# AUDIO_AMP.net
KiCad netlist of a schematic drawn in Altium Designer
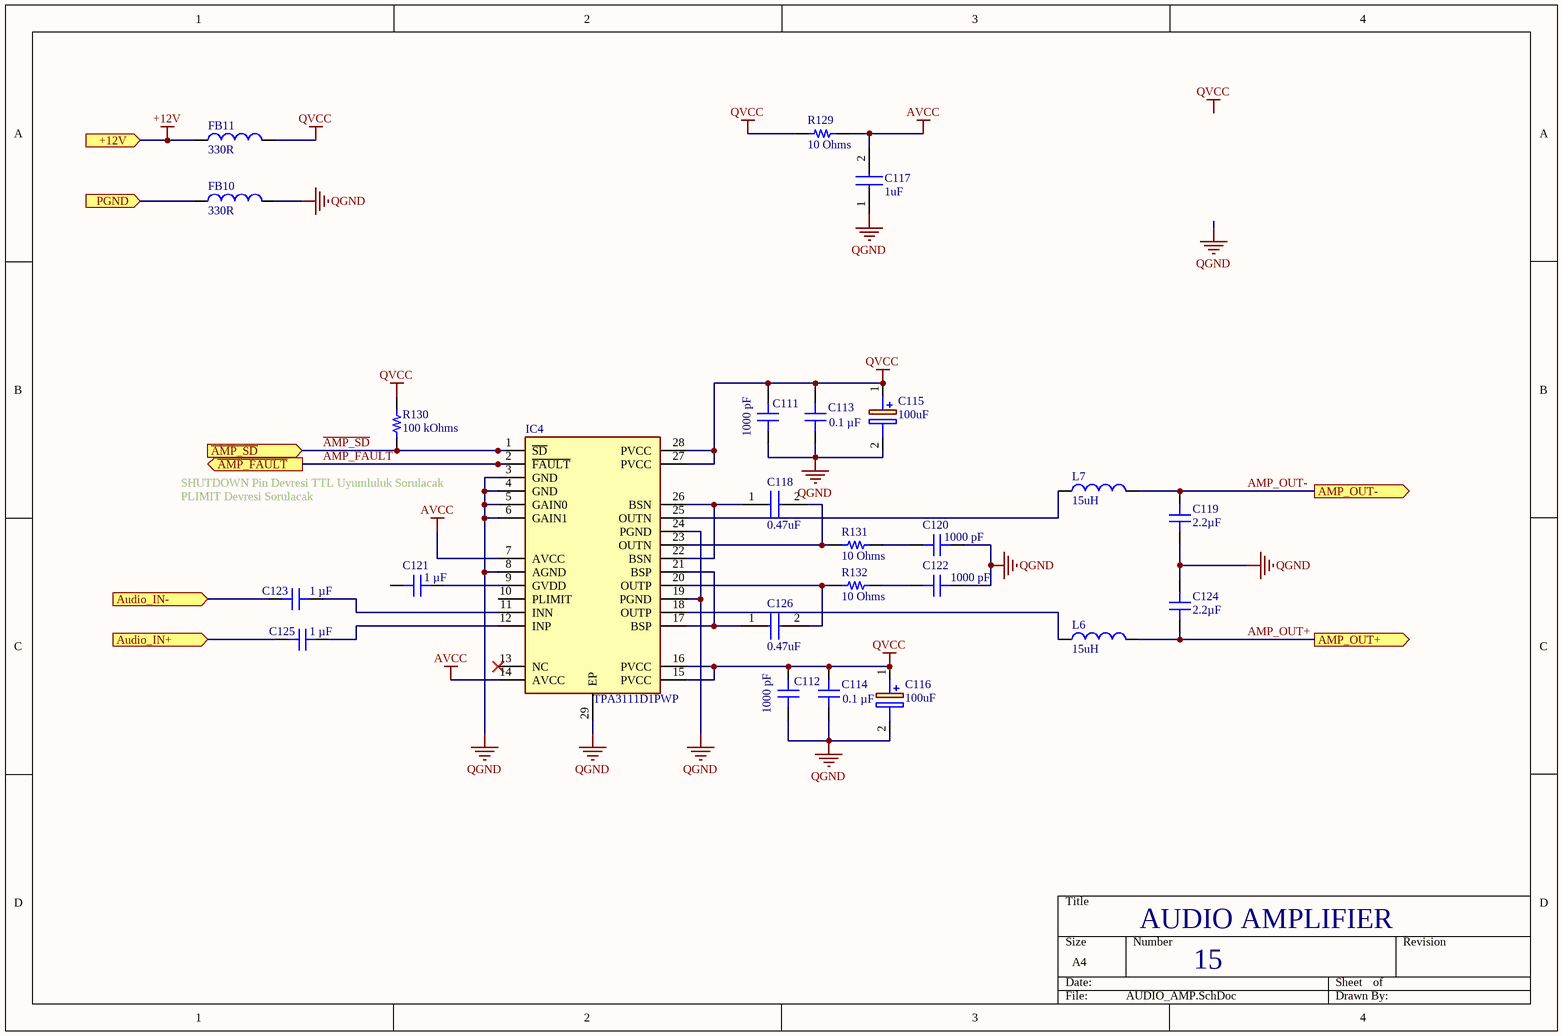
[diagram p0: AUDIO_AMP.SchDoc]

(export (version "E")
  (design (tool "Eeschema 10.0.6"))
  (components
    (comp (ref "C111")
      (value "1000 pF")
      (footprint "CAP 0603_1608")
      (description "CAP CER 1000PF 50V X8R 0603")
      (fields
        (field (name "PART NUMBER") "C1608X8R1H102K080AA")
        (field (name "MANUFACTURER") "TDK Corporation")
      )
      (libsource (lib "Celestial Altium Library") (part "Capacitor"))
    )
    (comp (ref "C112")
      (value "1000 pF")
      (footprint "CAP 0603_1608")
      (description "CAP CER 1000PF 50V X8R 0603")
      (fields
        (field (name "PART NUMBER") "C1608X8R1H102K080AA")
        (field (name "MANUFACTURER") "TDK Corporation")
      )
      (libsource (lib "Celestial Altium Library") (part "Capacitor"))
    )
    (comp (ref "C113")
      (value "0.1 µF")
      (footprint "CAP 0603_1608")
      (description "CAP CER 0.1UF 50V X7R 0603")
      (fields
        (field (name "PART NUMBER") "CGA3E2X7R1H104K080AE")
        (field (name "MANUFACTURER") "TDK Corporation")
      )
      (libsource (lib "Celestial Altium Library") (part "Capacitor"))
    )
    (comp (ref "C114")
      (value "0.1 µF")
      (footprint "CAP 0603_1608")
      (description "CAP CER 0.1UF 50V X7R 0603")
      (fields
        (field (name "PART NUMBER") "CGA3E2X7R1H104K080AE")
        (field (name "MANUFACTURER") "TDK Corporation")
      )
      (libsource (lib "Celestial Altium Library") (part "Capacitor"))
    )
    (comp (ref "C115")
      (value "100uF")
      (footprint "SamacSys:EEE0JA331XP")
      (description "Capacitor Polarised")
      (fields
        (field (name "MANUFACTURER_PART_NUMBER") "EEE-1VA101XP")
        (field (name "MOUSER PART NUMBER") "667-EEE-1VA101XP")
      )
      (libsource (lib "SamacSys") (part "EEE-1VA101XP"))
    )
    (comp (ref "C116")
      (value "100uF")
      (footprint "SamacSys:EEE0JA331XP")
      (description "Capacitor Polarised")
      (fields
        (field (name "MANUFACTURER_PART_NUMBER") "EEE-1VA101XP")
        (field (name "MOUSER PART NUMBER") "667-EEE-1VA101XP")
      )
      (libsource (lib "SamacSys") (part "EEE-1VA101XP"))
    )
    (comp (ref "C117")
      (value "1uF")
      (footprint "SamacSys:CAPC1608X90N")
      (description "Capacitor")
      (fields
        (field (name "MANUFACTURER_PART_NUMBER") "GMK107BJ105KA-T")
        (field (name "MOUSER PART NUMBER") "963-GMK107BJ105KA-T")
      )
      (libsource (lib "SamacSys") (part "GMK107BJ105KA-T"))
    )
    (comp (ref "C118")
      (value "0.47uF")
      (footprint "SamacSys:CAPC1608X90N")
      (description "Capacitor")
      (fields
        (field (name "MANUFACTURER_PART_NUMBER") "0603YD474KAT2A")
        (field (name "MOUSER PART NUMBER") "581-0603YD474K")
      )
      (libsource (lib "SamacSys") (part "0603YD474KAT2A"))
    )
    (comp (ref "C119")
      (value "2.2µF")
      (footprint "CAP 1206_3216 - 1.8MM")
      (description "CAP CER 2.2UF 50V X7R 1206")
      (fields (field (name "PART NUMBER") "12065C225K4T2A") (field (name "MANUFACTURER") "AVX Corporation"))
      (libsource (lib "Celestial Altium Library") (part "Capacitor"))
    )
    (comp (ref "C120")
      (value "1000 pF")
      (footprint "CAP 0603_1608")
      (description "CAP CER 1000PF 50V X8R 0603")
      (fields
        (field (name "PART NUMBER") "C1608X8R1H102K080AA")
        (field (name "MANUFACTURER") "TDK Corporation")
      )
      (libsource (lib "Celestial Altium Library") (part "Capacitor"))
    )
    (comp (ref "C121")
      (value "1 µF")
      (footprint "CAP 0603_1608")
      (description "CAP CER 1UF 16V X5R 0603")
      (fields (field (name "PART NUMBER") "C0603C105K4PAC7867") (field (name "MANUFACTURER") "KEMET"))
      (libsource (lib "Celestial Altium Library") (part "Capacitor"))
    )
    (comp (ref "C122")
      (value "1000 pF")
      (footprint "CAP 0603_1608")
      (description "CAP CER 1000PF 50V X8R 0603")
      (fields
        (field (name "PART NUMBER") "C1608X8R1H102K080AA")
        (field (name "MANUFACTURER") "TDK Corporation")
      )
      (libsource (lib "Celestial Altium Library") (part "Capacitor"))
    )
    (comp (ref "C123")
      (value "1 µF")
      (footprint "CAP 0603_1608")
      (description "CAP CER 1UF 16V X5R 0603")
      (fields (field (name "PART NUMBER") "C0603C105K4PAC7867") (field (name "MANUFACTURER") "KEMET"))
      (libsource (lib "Celestial Altium Library") (part "Capacitor"))
    )
    (comp (ref "C124")
      (value "2.2µF")
      (footprint "CAP 1206_3216 - 1.8MM")
      (description "CAP CER 2.2UF 50V X7R 1206")
      (fields (field (name "PART NUMBER") "12065C225K4T2A") (field (name "MANUFACTURER") "AVX Corporation"))
      (libsource (lib "Celestial Altium Library") (part "Capacitor"))
    )
    (comp (ref "C125")
      (value "1 µF")
      (footprint "CAP 0603_1608")
      (description "CAP CER 1UF 16V X5R 0603")
      (fields (field (name "PART NUMBER") "C0603C105K4PAC7867") (field (name "MANUFACTURER") "KEMET"))
      (libsource (lib "Celestial Altium Library") (part "Capacitor"))
    )
    (comp (ref "C126")
      (value "0.47uF")
      (footprint "SamacSys:CAPC1608X90N")
      (description "Capacitor")
      (fields
        (field (name "MANUFACTURER_PART_NUMBER") "0603YD474KAT2A")
        (field (name "MOUSER PART NUMBER") "581-0603YD474K")
      )
      (libsource (lib "SamacSys") (part "0603YD474KAT2A"))
    )
    (comp (ref "FB10")
      (value "330R")
      (footprint "FB0805")
      (description "FERRITE BEAD 330 OHM 0805 1LN")
      (libsource (lib "ECU") (part "FB0805_330R@100MHz"))
    )
    (comp (ref "FB11")
      (value "330R")
      (footprint "FB0805")
      (description "FERRITE BEAD 330 OHM 0805 1LN")
      (libsource (lib "ECU") (part "FB0805_330R@100MHz"))
    )
    (comp (ref "IC4")
      (value "TPA3111D1PWP")
      (footprint "SOP65P640X120-29N")
      (description "Integrated Circuit")
      (fields (field (name "MOUSER PART NUMBER") "595-TPA3111D1PWP"))
      (libsource (lib "SamacSys") (part "TPA3111D1PWP"))
    )
    (comp (ref "L6")
      (value "15uH")
      (footprint "IND_DG6045C")
      (description "FIXED IND 15UH 2.5A 75.6 MOHM")
      (libsource (lib "ECU") (part "IND_1255AY-150M=P3"))
    )
    (comp (ref "L7")
      (value "15uH")
      (footprint "IND_DG6045C")
      (description "FIXED IND 15UH 2.5A 75.6 MOHM")
      (libsource (lib "ECU") (part "IND_1255AY-150M=P3"))
    )
    (comp (ref "R129")
      (value "10 Ohms")
      (footprint "RES 1206_3216")
      (description "RESISTOR THICK FILM 1206")
      (fields
        (field (name "PART NUMBER") "RK73G2BTTD10R0F")
        (field (name "MANUFACTURER") "KOA Speer Electronics, Inc.")
      )
      (libsource (lib "Celestial Altium Library") (part "Resistor"))
    )
    (comp (ref "R130")
      (value "100 kOhms")
      (footprint "RES 0603_1608")
      (description "RES 100K OHM 5% 1/10W 0603")
      (fields
        (field (name "PART NUMBER") "RMCF0603JT100K")
        (field (name "MANUFACTURER") "Stackpole Electronics Inc")
      )
      (libsource (lib "Celestial Altium Library") (part "Resistor"))
    )
    (comp (ref "R131")
      (value "10 Ohms")
      (footprint "RES 0805_2012")
      (description "RCC0805 100 10R 1% ET1 E3")
      (fields (field (name "PART NUMBER") "RCC080510R0FKEA") (field (name "MANUFACTURER") "Vishay Dale"))
      (libsource (lib "Celestial Altium Library") (part "Resistor"))
    )
    (comp (ref "R132")
      (value "10 Ohms")
      (footprint "RES 0805_2012")
      (description "RCC0805 100 10R 1% ET1 E3")
      (fields (field (name "PART NUMBER") "RCC080510R0FKEA") (field (name "MANUFACTURER") "Vishay Dale"))
      (libsource (lib "Celestial Altium Library") (part "Resistor"))
    )
  )
  (nets
    (net (code "1") (name "+12V") (class "Default")
      (node (ref "FB11") (pin "1") (pinfunction "1_1") (pintype "passive"))
    )
    (net (code "2") (name "/AMP_OUT+") (class "Default")
      (node (ref "C124") (pin "1") (pinfunction "1_1") (pintype "passive"))
      (node (ref "L6") (pin "2") (pinfunction "2_2") (pintype "passive"))
    )
    (net (code "3") (name "/AMP_OUT-") (class "Default")
      (node (ref "C119") (pin "2") (pinfunction "2_2") (pintype "passive"))
      (node (ref "L7") (pin "2") (pinfunction "2_2") (pintype "passive"))
    )
    (net (code "4") (name "/Audio_IN+") (class "Default")
      (node (ref "C125") (pin "1") (pinfunction "1_1") (pintype "passive"))
    )
    (net (code "5") (name "/Audio_IN-") (class "Default")
      (node (ref "C123") (pin "1") (pinfunction "1_1") (pintype "passive"))
    )
    (net (code "6") (name "/PGND") (class "Default")
      (node (ref "FB10") (pin "1") (pinfunction "1_1") (pintype "passive"))
    )
    (net (code "7") (name "/~{AMP_FAULT}") (class "Default")
      (node (ref "IC4") (pin "2") (pinfunction "~{FAULT}_2") (pintype "passive"))
    )
    (net (code "8") (name "/~{AMP_SD}") (class "Default")
      (node (ref "IC4") (pin "1") (pinfunction "~{SD}_1") (pintype "passive"))
      (node (ref "R130") (pin "1") (pinfunction "1_1") (pintype "passive"))
    )
    (net (code "9") (name "AVCC") (class "Default")
      (node (ref "C117") (pin "2") (pinfunction "2_2") (pintype "passive"))
      (node (ref "IC4") (pin "14") (pinfunction "AVCC_14") (pintype "passive"))
      (node (ref "IC4") (pin "7") (pinfunction "AVCC_7") (pintype "passive"))
      (node (ref "R129") (pin "2") (pinfunction "2_2") (pintype "passive"))
    )
    (net (code "10") (name "Net-(C118-Pad1)") (class "Default")
      (node (ref "C118") (pin "1") (pinfunction "1_1") (pintype "passive"))
      (node (ref "IC4") (pin "22") (pinfunction "BSN_22") (pintype "passive"))
      (node (ref "IC4") (pin "26") (pinfunction "BSN_26") (pintype "passive"))
    )
    (net (code "11") (name "Net-(C118-Pad2)") (class "Default")
      (node (ref "C118") (pin "2") (pinfunction "2_2") (pintype "passive"))
      (node (ref "IC4") (pin "23") (pinfunction "OUTN_23") (pintype "passive"))
      (node (ref "R131") (pin "1") (pinfunction "1_1") (pintype "passive"))
    )
    (net (code "12") (name "Net-(C120-Pad1)") (class "Default")
      (node (ref "C120") (pin "1") (pinfunction "1_1") (pintype "passive"))
      (node (ref "R131") (pin "2") (pinfunction "2_2") (pintype "passive"))
    )
    (net (code "13") (name "Net-(C122-Pad1)") (class "Default")
      (node (ref "C122") (pin "1") (pinfunction "1_1") (pintype "passive"))
      (node (ref "R132") (pin "2") (pinfunction "2_2") (pintype "passive"))
    )
    (net (code "14") (name "Net-(C126-Pad1)") (class "Default")
      (node (ref "C126") (pin "1") (pinfunction "1_1") (pintype "passive"))
      (node (ref "IC4") (pin "17") (pinfunction "BSP_17") (pintype "passive"))
      (node (ref "IC4") (pin "21") (pinfunction "BSP_21") (pintype "passive"))
    )
    (net (code "15") (name "Net-(C126-Pad2)") (class "Default")
      (node (ref "C126") (pin "2") (pinfunction "2_2") (pintype "passive"))
      (node (ref "IC4") (pin "20") (pinfunction "OUTP_20") (pintype "passive"))
      (node (ref "R132") (pin "1") (pinfunction "1_1") (pintype "passive"))
    )
    (net (code "16") (name "Net-(IC4-GVDD)") (class "Default")
      (node (ref "C121") (pin "2") (pinfunction "2_2") (pintype "passive"))
      (node (ref "IC4") (pin "9") (pinfunction "GVDD_9") (pintype "passive"))
    )
    (net (code "17") (name "Net-(IC4-INN)") (class "Default")
      (node (ref "C123") (pin "2") (pinfunction "2_2") (pintype "passive"))
      (node (ref "IC4") (pin "11") (pinfunction "INN_11") (pintype "passive"))
    )
    (net (code "18") (name "Net-(IC4-INP)") (class "Default")
      (node (ref "C125") (pin "2") (pinfunction "2_2") (pintype "passive"))
      (node (ref "IC4") (pin "12") (pinfunction "INP_12") (pintype "passive"))
    )
    (net (code "19") (name "Net-(IC4-OUTN-Pad25)") (class "Default")
      (node (ref "IC4") (pin "25") (pinfunction "OUTN_25") (pintype "passive"))
      (node (ref "L7") (pin "1") (pinfunction "1_1") (pintype "passive"))
    )
    (net (code "20") (name "Net-(IC4-OUTP-Pad18)") (class "Default")
      (node (ref "IC4") (pin "18") (pinfunction "OUTP_18") (pintype "passive"))
      (node (ref "L6") (pin "1") (pinfunction "1_1") (pintype "passive"))
    )
    (net (code "21") (name "QGND") (class "Default")
      (node (ref "C111") (pin "1") (pinfunction "1_1") (pintype "passive"))
      (node (ref "C112") (pin "1") (pinfunction "1_1") (pintype "passive"))
      (node (ref "C113") (pin "1") (pinfunction "1_1") (pintype "passive"))
      (node (ref "C114") (pin "1") (pinfunction "1_1") (pintype "passive"))
      (node (ref "C115") (pin "2") (pinfunction "-_2") (pintype "passive"))
      (node (ref "C116") (pin "2") (pinfunction "-_2") (pintype "passive"))
      (node (ref "C117") (pin "1") (pinfunction "1_1") (pintype "passive"))
      (node (ref "C119") (pin "1") (pinfunction "1_1") (pintype "passive"))
      (node (ref "C120") (pin "2") (pinfunction "2_2") (pintype "passive"))
      (node (ref "C122") (pin "2") (pinfunction "2_2") (pintype "passive"))
      (node (ref "C124") (pin "2") (pinfunction "2_2") (pintype "passive"))
      (node (ref "FB10") (pin "2") (pinfunction "2_2") (pintype "passive"))
      (node (ref "IC4") (pin "19") (pinfunction "PGND_19") (pintype "passive"))
      (node (ref "IC4") (pin "24") (pinfunction "PGND_24") (pintype "passive"))
      (node (ref "IC4") (pin "29") (pinfunction "EP_29") (pintype "passive"))
      (node (ref "IC4") (pin "3") (pinfunction "GND_3") (pintype "passive"))
      (node (ref "IC4") (pin "4") (pinfunction "GND_4") (pintype "passive"))
      (node (ref "IC4") (pin "5") (pinfunction "GAIN0_5") (pintype "passive"))
      (node (ref "IC4") (pin "6") (pinfunction "GAIN1_6") (pintype "passive"))
      (node (ref "IC4") (pin "8") (pinfunction "AGND_8") (pintype "passive"))
    )
    (net (code "22") (name "QVCC") (class "Default")
      (node (ref "C111") (pin "2") (pinfunction "2_2") (pintype "passive"))
      (node (ref "C112") (pin "2") (pinfunction "2_2") (pintype "passive"))
      (node (ref "C113") (pin "2") (pinfunction "2_2") (pintype "passive"))
      (node (ref "C114") (pin "2") (pinfunction "2_2") (pintype "passive"))
      (node (ref "C115") (pin "1") (pinfunction "+_1") (pintype "passive"))
      (node (ref "C116") (pin "1") (pinfunction "+_1") (pintype "passive"))
      (node (ref "FB11") (pin "2") (pinfunction "2_2") (pintype "passive"))
      (node (ref "IC4") (pin "15") (pinfunction "PVCC_15") (pintype "passive"))
      (node (ref "IC4") (pin "16") (pinfunction "PVCC_16") (pintype "passive"))
      (node (ref "IC4") (pin "27") (pinfunction "PVCC_27") (pintype "passive"))
      (node (ref "IC4") (pin "28") (pinfunction "PVCC_28") (pintype "passive"))
      (node (ref "R129") (pin "1") (pinfunction "1_1") (pintype "passive"))
      (node (ref "R130") (pin "2") (pinfunction "2_2") (pintype "passive"))
    )
    (net (code "23") (name "unconnected-(C121-Pad1)") (class "Default")
      (node (ref "C121") (pin "1") (pinfunction "1_1") (pintype "passive"))
    )
    (net (code "24") (name "unconnected-(IC4-NC-Pad13)") (class "Default")
      (node (ref "IC4") (pin "13") (pinfunction "NC_13") (pintype "passive+no_connect"))
    )
    (net (code "25") (name "unconnected-(IC4-PLIMIT-Pad10)") (class "Default")
      (node (ref "IC4") (pin "10") (pinfunction "PLIMIT_10") (pintype "passive"))
    )
  )
)
